# LightLink_V4.net
KiCad netlist of a schematic drawn in Altium Designer
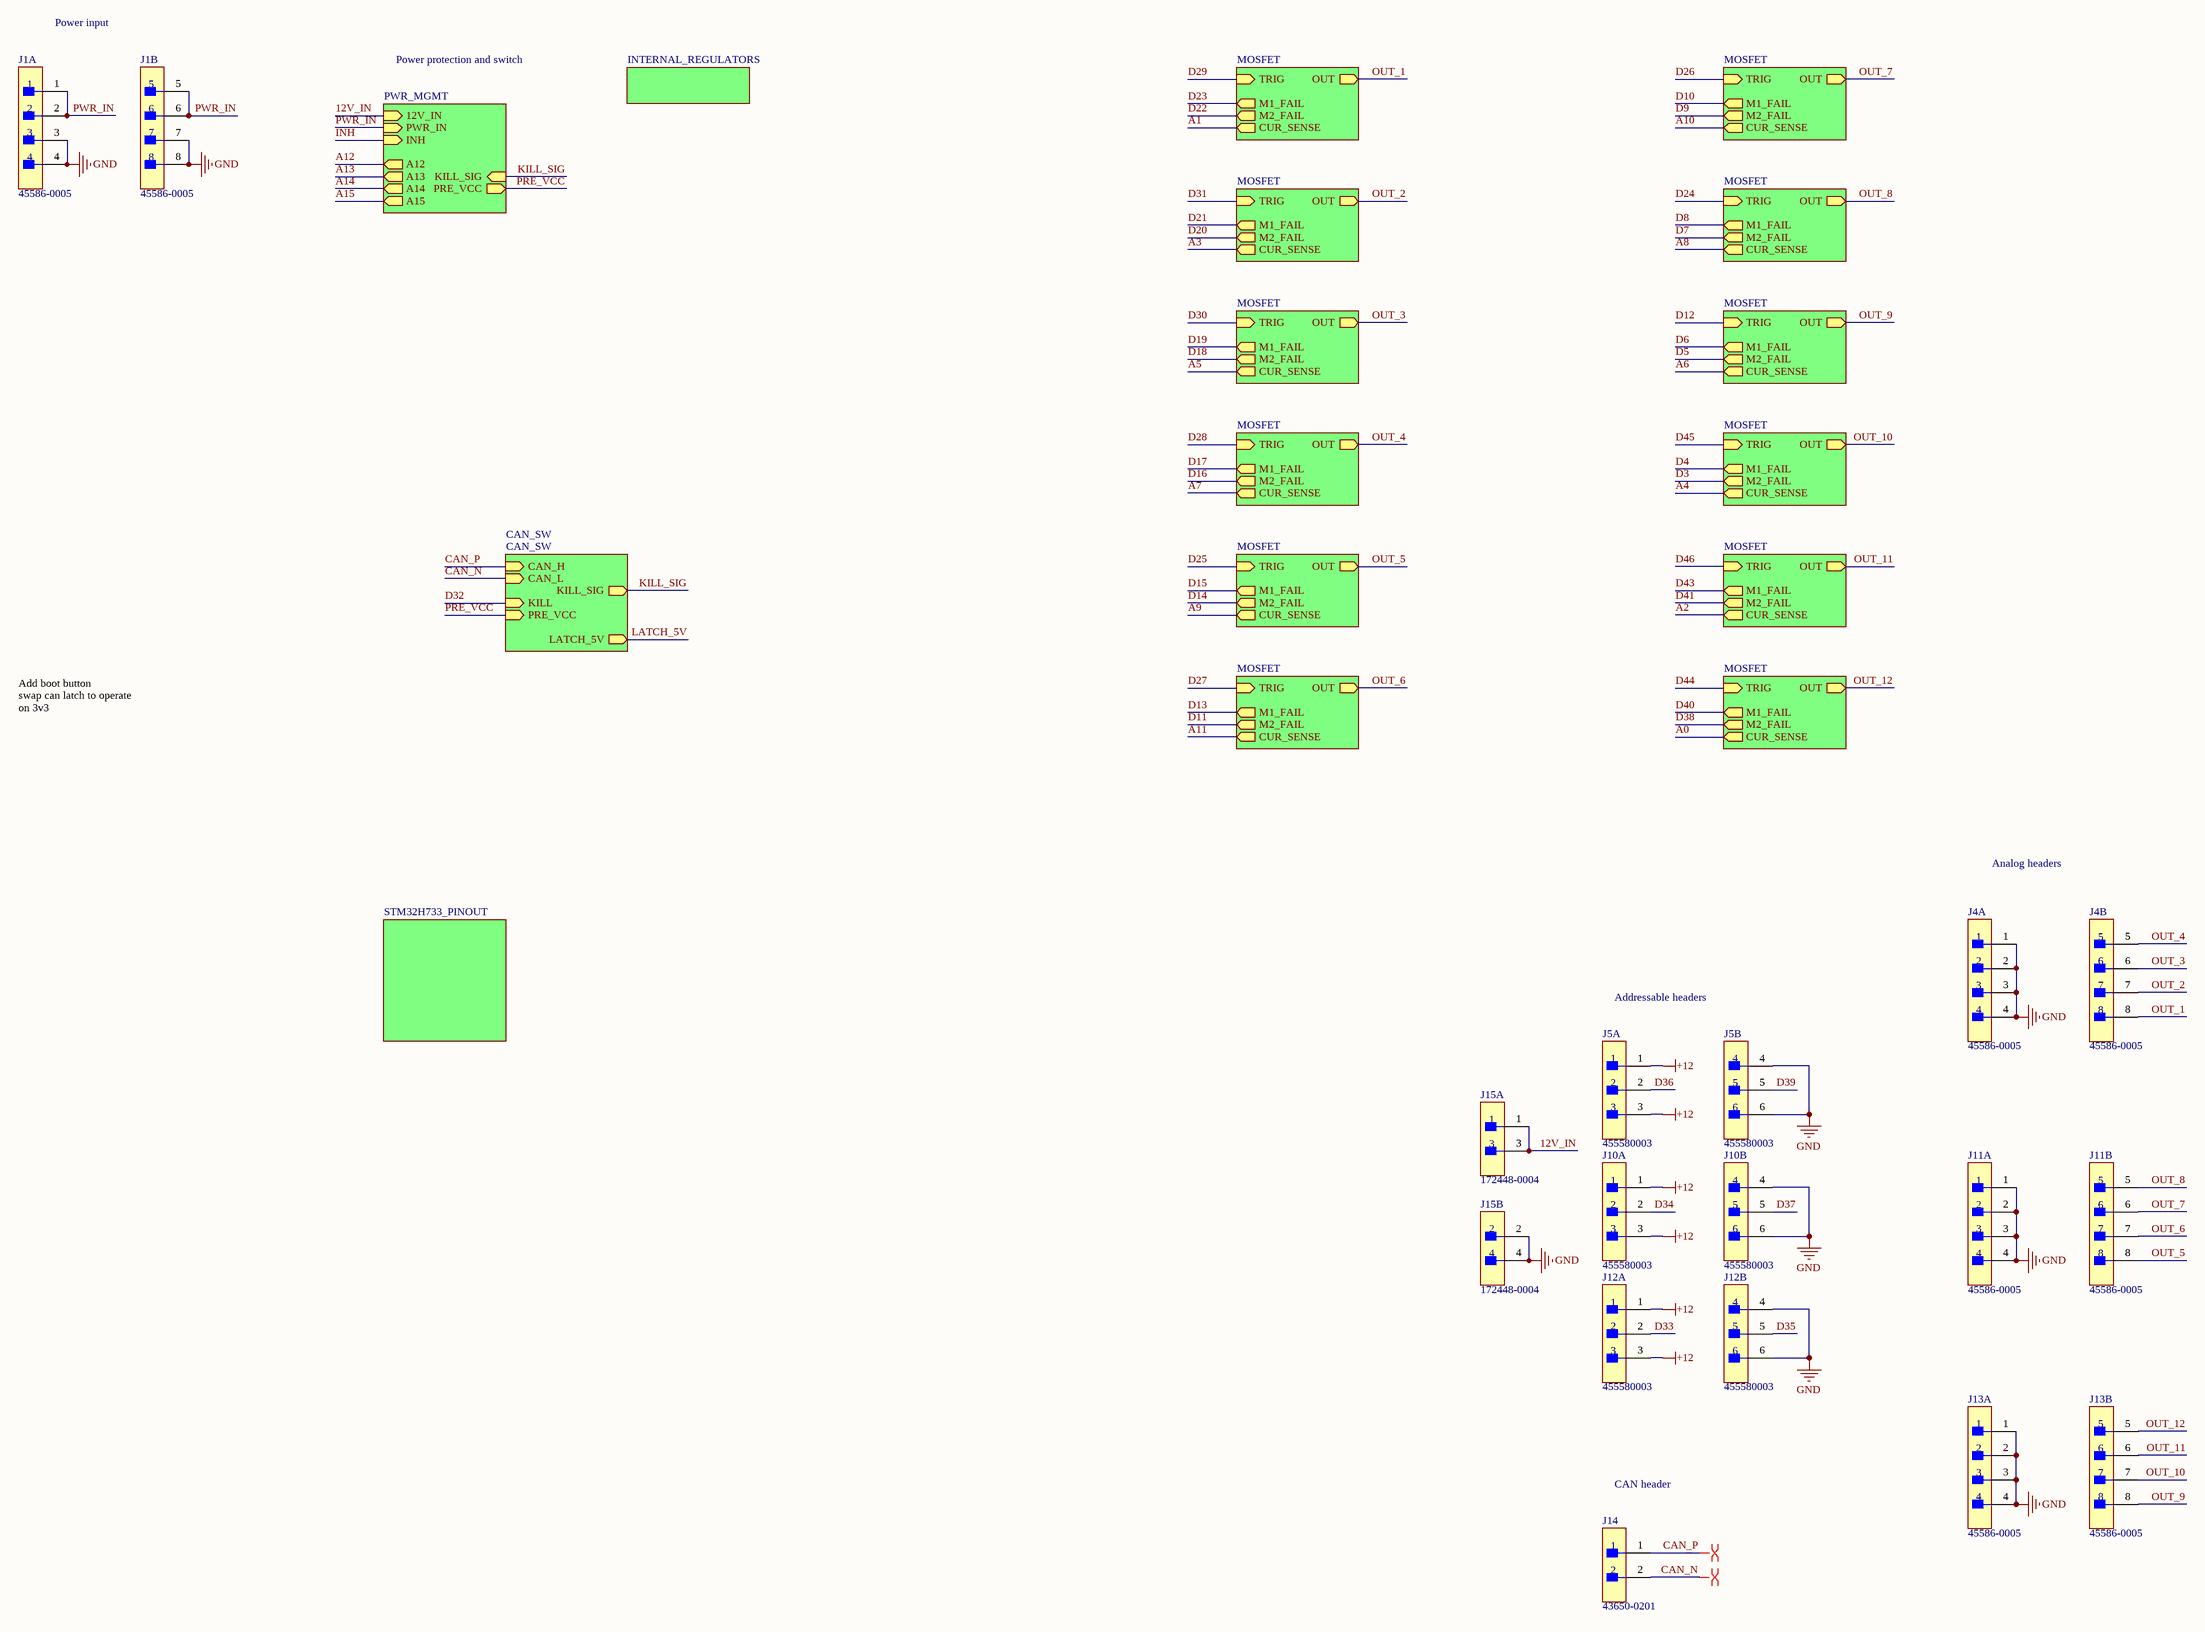
[diagram p0: LightLink_V4.SchDoc]

(export (version "E")
  (design (tool "Eeschema 10.0.6"))
  (components
    (comp (ref "J1")
      (value "45586-0005")
      (footprint "FP-45586-0005-MFG")
      (description "CONN HEADER R/A 8POS 4.2MM")
      (libsource (lib "Altium Content Vault") (part "85438c39ca9ef07d43bb2e97c52bc44"))
    )
    (comp (ref "J4")
      (value "45586-0005")
      (footprint "FP-45586-0005-MFG")
      (description "CONN HEADER R/A 8POS 4.2MM")
      (libsource (lib "Altium Content Vault") (part "85438c39ca9ef07d43bb2e97c52bc44"))
    )
    (comp (ref "J5")
      (value "455580003")
      (footprint "FP-455580003-MFG")
      (description "CONN HEADER R/A 6POS 4.2MM")
      (fields
        (field (name "OCTOPART") "https://octopart.com/45558-0003-molex-7672845")
        (field (name "MANUFACTURER") "Molex")
      )
      (libsource (lib "Altium Content Vault") (part "bb9cbdb24149a20ba329b4e86909569"))
    )
    (comp (ref "J10")
      (value "455580003")
      (footprint "FP-455580003-MFG")
      (description "CONN HEADER R/A 6POS 4.2MM")
      (fields
        (field (name "OCTOPART") "https://octopart.com/45558-0003-molex-7672845")
        (field (name "MANUFACTURER") "Molex")
      )
      (libsource (lib "Altium Content Vault") (part "bb9cbdb24149a20ba329b4e86909569"))
    )
    (comp (ref "J11")
      (value "45586-0005")
      (footprint "FP-45586-0005-MFG")
      (description "CONN HEADER R/A 8POS 4.2MM")
      (libsource (lib "Altium Content Vault") (part "85438c39ca9ef07d43bb2e97c52bc44"))
    )
    (comp (ref "J12")
      (value "455580003")
      (footprint "FP-455580003-MFG")
      (description "CONN HEADER R/A 6POS 4.2MM")
      (fields
        (field (name "OCTOPART") "https://octopart.com/45558-0003-molex-7672845")
        (field (name "MANUFACTURER") "Molex")
      )
      (libsource (lib "Altium Content Vault") (part "bb9cbdb24149a20ba329b4e86909569"))
    )
    (comp (ref "J13")
      (value "45586-0005")
      (footprint "FP-45586-0005-MFG")
      (description "CONN HEADER R/A 8POS 4.2MM")
      (libsource (lib "Altium Content Vault") (part "85438c39ca9ef07d43bb2e97c52bc44"))
    )
    (comp (ref "J14")
      (value "43650-0201")
      (footprint "FP-43650-0201-MFG")
      (description "CONN HEADER R/A 2POS 3MM")
      (libsource (lib "Altium Content Vault") (part "3bc925449376181038e59eaffc5286c"))
    )
    (comp (ref "J15")
      (value "172448-0004")
      (footprint "FP-39-30-1041-MFG")
      (description "Different component but holes should line up. Original P/N is 39-30-1041")
      (fields
        (field (name "MANUFACTURER") "Molex")
        (field (name "OCTOPART") "https://octopart.com/39-30-1041-molex-276737")
      )
      (libsource (lib "Altium Content Vault") (part "1621473add15499e993d6bbd36d0f06"))
    )
  )
  (nets
    (net (code "1") (name "+12") (class "Default")
      (node (ref "J10") (pin "1") (pinfunction "1_1") (pintype "passive"))
      (node (ref "J10") (pin "3") (pinfunction "3_3") (pintype "passive"))
      (node (ref "J12") (pin "1") (pinfunction "1_1") (pintype "passive"))
      (node (ref "J12") (pin "3") (pinfunction "3_3") (pintype "passive"))
      (node (ref "J5") (pin "1") (pinfunction "1_1") (pintype "passive"))
      (node (ref "J5") (pin "3") (pinfunction "3_3") (pintype "passive"))
    )
    (net (code "2") (name "/12V_IN") (class "Default")
      (node (ref "J15") (pin "1") (pinfunction "1_1") (pintype "passive"))
      (node (ref "J15") (pin "3") (pinfunction "3_3") (pintype "passive"))
    )
    (net (code "19") (name "/CAN_N") (class "Default")
      (node (ref "J14") (pin "2") (pinfunction "2_2") (pintype "passive"))
    )
    (net (code "20") (name "/CAN_P") (class "Default")
      (node (ref "J14") (pin "1") (pinfunction "1_1") (pintype "passive"))
    )
    (net (code "51") (name "/D33") (class "Default")
      (node (ref "J12") (pin "2") (pinfunction "2_2") (pintype "passive"))
    )
    (net (code "52") (name "/D34") (class "Default")
      (node (ref "J10") (pin "2") (pinfunction "2_2") (pintype "passive"))
    )
    (net (code "53") (name "/D35") (class "Default")
      (node (ref "J12") (pin "5") (pinfunction "5_5") (pintype "passive"))
    )
    (net (code "54") (name "/D36") (class "Default")
      (node (ref "J5") (pin "2") (pinfunction "2_2") (pintype "passive"))
    )
    (net (code "55") (name "/D37") (class "Default")
      (node (ref "J10") (pin "5") (pinfunction "5_5") (pintype "passive"))
    )
    (net (code "57") (name "/D39") (class "Default")
      (node (ref "J5") (pin "5") (pinfunction "5_5") (pintype "passive"))
    )
    (net (code "67") (name "/OUT_1") (class "Default")
      (node (ref "J4") (pin "8") (pinfunction "8_8") (pintype "passive"))
    )
    (net (code "68") (name "/OUT_2") (class "Default")
      (node (ref "J4") (pin "7") (pinfunction "7_7") (pintype "passive"))
    )
    (net (code "69") (name "/OUT_3") (class "Default")
      (node (ref "J4") (pin "6") (pinfunction "6_6") (pintype "passive"))
    )
    (net (code "70") (name "/OUT_4") (class "Default")
      (node (ref "J4") (pin "5") (pinfunction "5_5") (pintype "passive"))
    )
    (net (code "71") (name "/OUT_5") (class "Default")
      (node (ref "J11") (pin "8") (pinfunction "8_8") (pintype "passive"))
    )
    (net (code "72") (name "/OUT_6") (class "Default")
      (node (ref "J11") (pin "7") (pinfunction "7_7") (pintype "passive"))
    )
    (net (code "73") (name "/OUT_7") (class "Default")
      (node (ref "J11") (pin "6") (pinfunction "6_6") (pintype "passive"))
    )
    (net (code "74") (name "/OUT_8") (class "Default")
      (node (ref "J11") (pin "5") (pinfunction "5_5") (pintype "passive"))
    )
    (net (code "75") (name "/OUT_9") (class "Default")
      (node (ref "J13") (pin "8") (pinfunction "8_8") (pintype "passive"))
    )
    (net (code "76") (name "/OUT_10") (class "Default")
      (node (ref "J13") (pin "7") (pinfunction "7_7") (pintype "passive"))
    )
    (net (code "77") (name "/OUT_11") (class "Default")
      (node (ref "J13") (pin "6") (pinfunction "6_6") (pintype "passive"))
    )
    (net (code "78") (name "/OUT_12") (class "Default")
      (node (ref "J13") (pin "5") (pinfunction "5_5") (pintype "passive"))
    )
    (net (code "80") (name "/PWR_IN") (class "Default")
      (node (ref "J1") (pin "1") (pinfunction "1_1") (pintype "passive"))
      (node (ref "J1") (pin "2") (pinfunction "2_2") (pintype "passive"))
      (node (ref "J1") (pin "5") (pinfunction "5_5") (pintype "passive"))
      (node (ref "J1") (pin "6") (pinfunction "6_6") (pintype "passive"))
    )
    (net (code "81") (name "GND") (class "Default")
      (node (ref "J1") (pin "3") (pinfunction "3_3") (pintype "passive"))
      (node (ref "J1") (pin "4") (pinfunction "4_4") (pintype "passive"))
      (node (ref "J1") (pin "7") (pinfunction "7_7") (pintype "passive"))
      (node (ref "J1") (pin "8") (pinfunction "8_8") (pintype "passive"))
      (node (ref "J10") (pin "4") (pinfunction "4_4") (pintype "passive"))
      (node (ref "J10") (pin "6") (pinfunction "6_6") (pintype "passive"))
      (node (ref "J11") (pin "1") (pinfunction "1_1") (pintype "passive"))
      (node (ref "J11") (pin "2") (pinfunction "2_2") (pintype "passive"))
      (node (ref "J11") (pin "3") (pinfunction "3_3") (pintype "passive"))
      (node (ref "J11") (pin "4") (pinfunction "4_4") (pintype "passive"))
      (node (ref "J12") (pin "4") (pinfunction "4_4") (pintype "passive"))
      (node (ref "J12") (pin "6") (pinfunction "6_6") (pintype "passive"))
      (node (ref "J13") (pin "1") (pinfunction "1_1") (pintype "passive"))
      (node (ref "J13") (pin "2") (pinfunction "2_2") (pintype "passive"))
      (node (ref "J13") (pin "3") (pinfunction "3_3") (pintype "passive"))
      (node (ref "J13") (pin "4") (pinfunction "4_4") (pintype "passive"))
      (node (ref "J15") (pin "2") (pinfunction "2_2") (pintype "passive"))
      (node (ref "J15") (pin "4") (pinfunction "4_4") (pintype "passive"))
      (node (ref "J4") (pin "1") (pinfunction "1_1") (pintype "passive"))
      (node (ref "J4") (pin "2") (pinfunction "2_2") (pintype "passive"))
      (node (ref "J4") (pin "3") (pinfunction "3_3") (pintype "passive"))
      (node (ref "J4") (pin "4") (pinfunction "4_4") (pintype "passive"))
      (node (ref "J5") (pin "4") (pinfunction "4_4") (pintype "passive"))
      (node (ref "J5") (pin "6") (pinfunction "6_6") (pintype "passive"))
    )
  )
)
